# schematic.net
KiCad netlist of a schematic drawn in EasyEDA
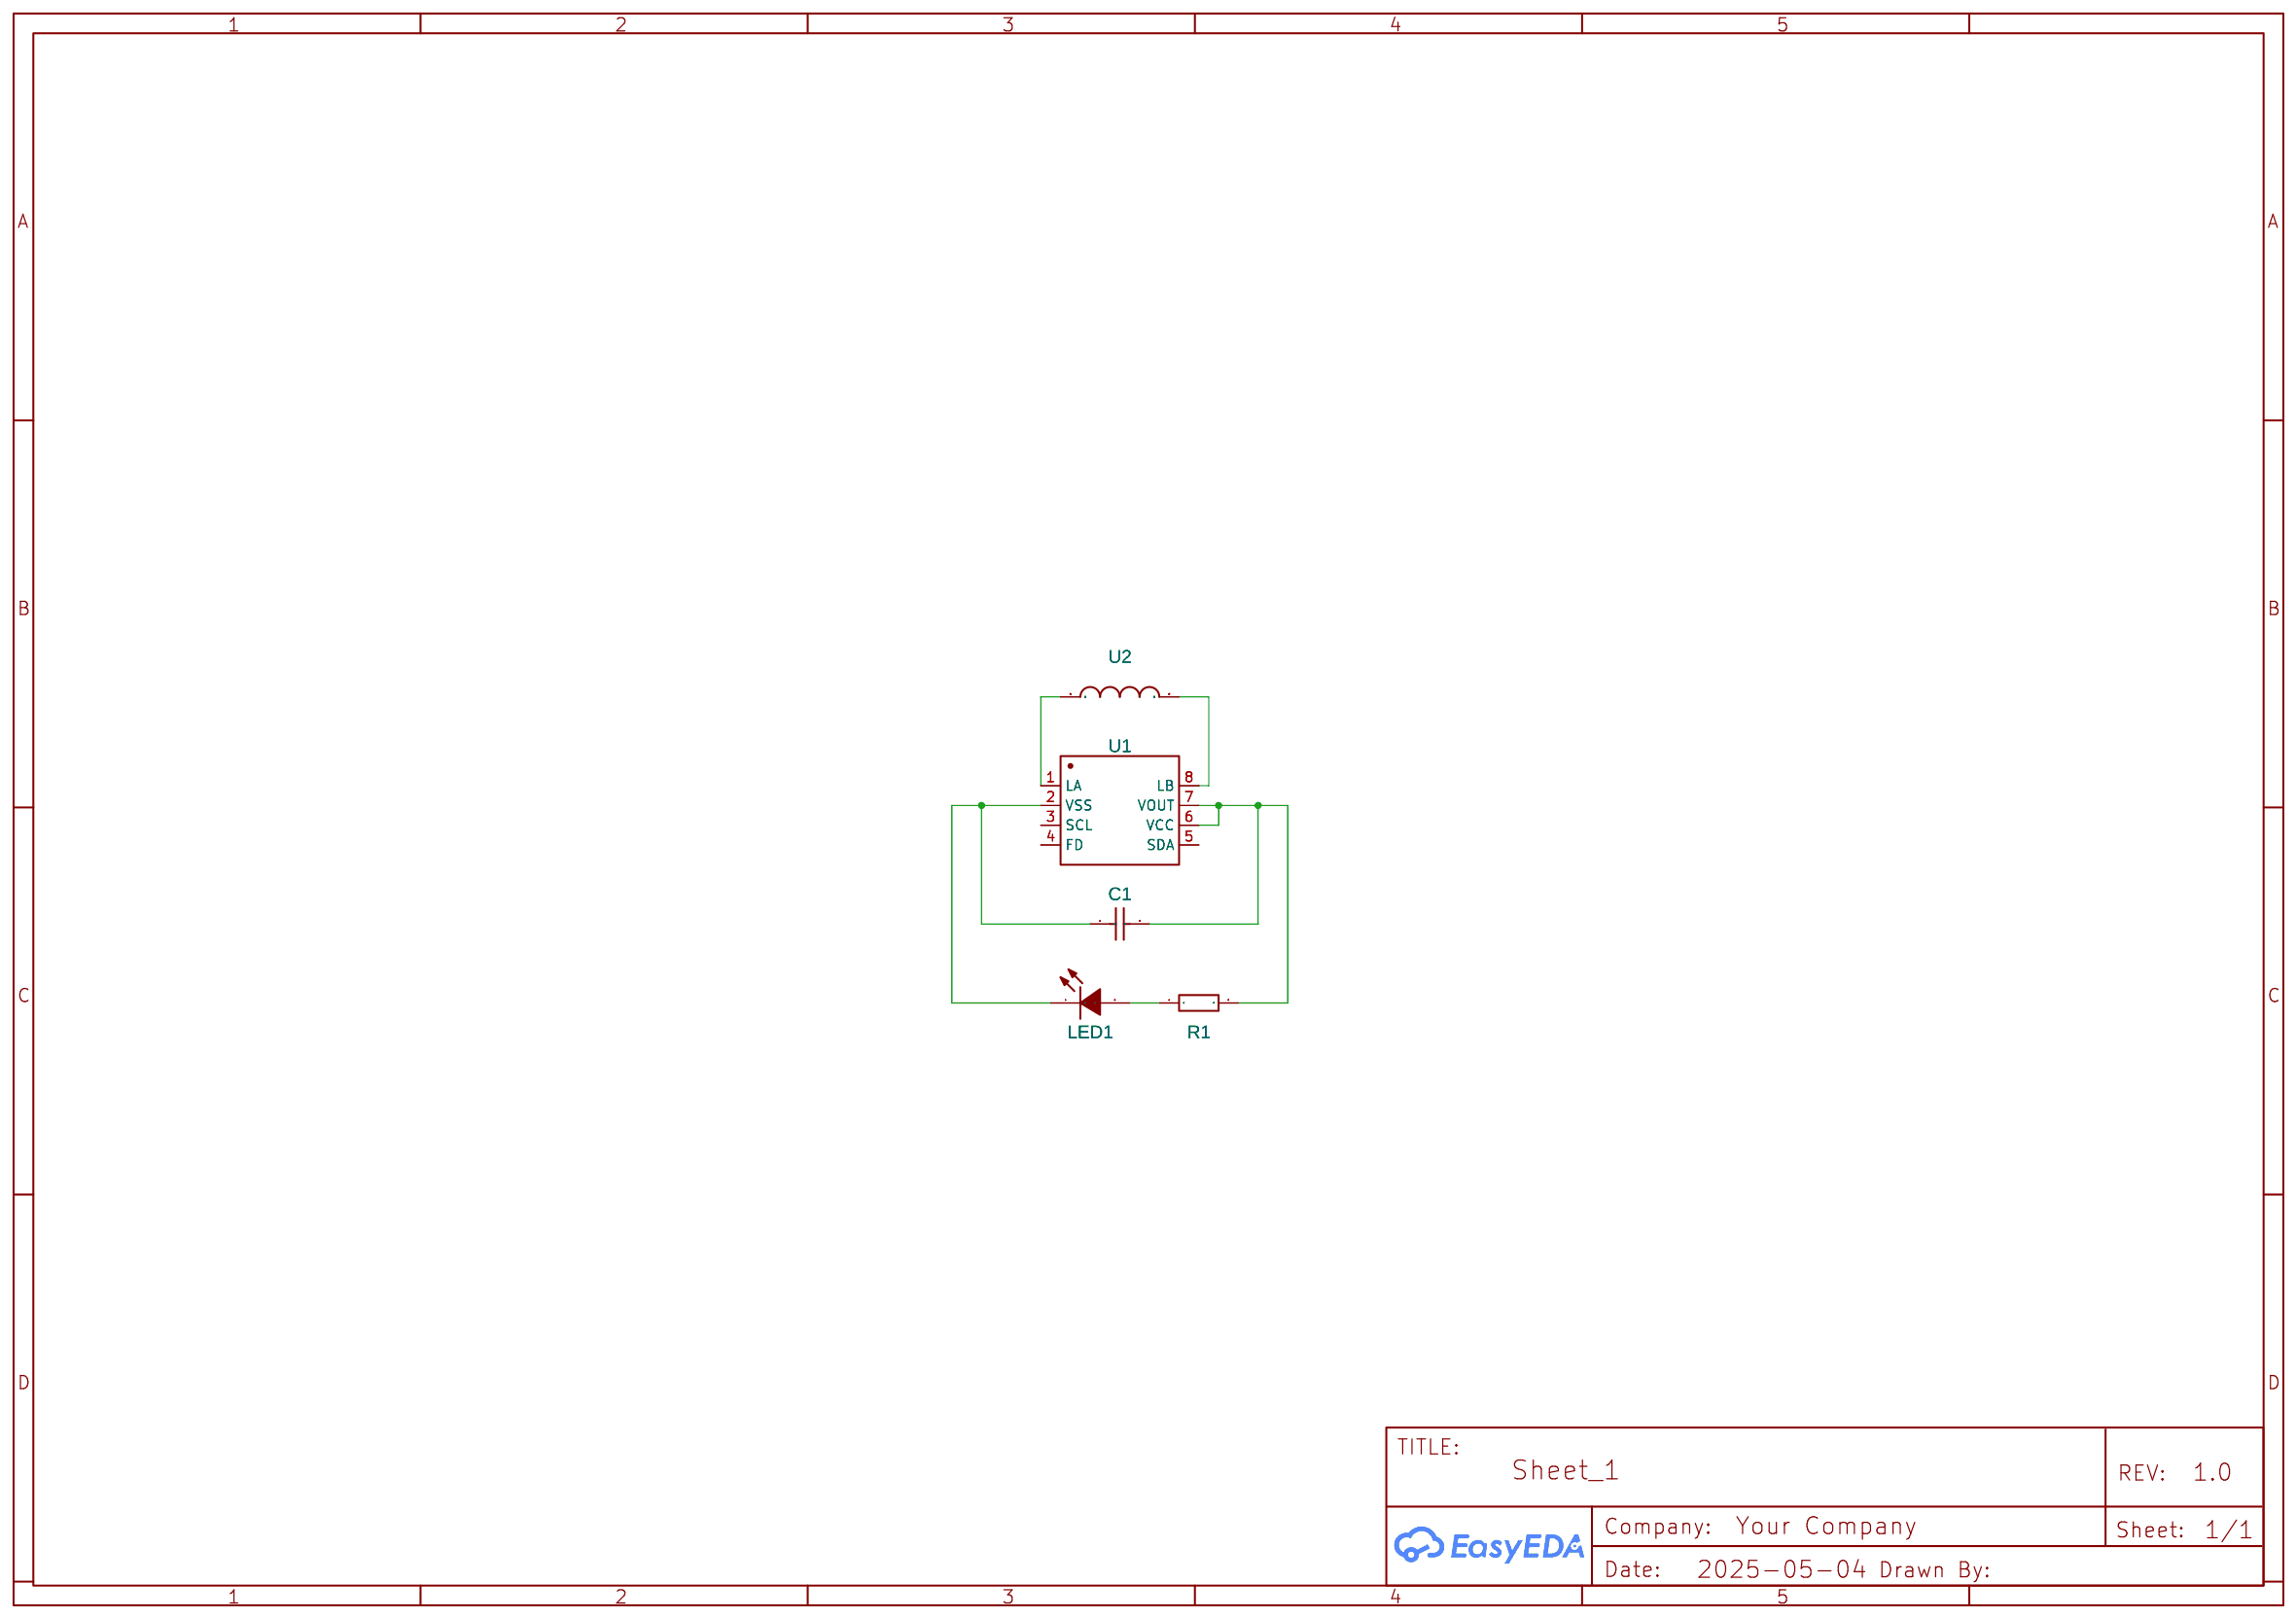
[diagram p0: schematic sheet]

(export (version "E")
  (design (tool "Eeschema 10.0.6"))
  (components
    (comp (ref "C1")
      (value "220nF")
      (fields
        (field (name "Manufacturer Part") "CL10B224KA8NNNC")
        (field (name "Manufacturer") "SAMSUNG(三星)")
      )
      (libsource (lib "") (part "CL10B224KA8NNNC"))
    )
    (comp (ref "LED1")
      (value "LTST-C191KSKT")
      (fields (field (name "Manufacturer") "LITEON(光宝)"))
      (libsource (lib "") (part "LTST-C191KSKT"))
    )
    (comp (ref "R1")
      (value "47Ω")
      (fields
        (field (name "Manufacturer Part") "0603WAF470JT5E")
        (field (name "Manufacturer") "UNI-ROYAL(厚声)")
      )
      (libsource (lib "") (part "0603WAF470JT5E"))
    )
    (comp (ref "U1")
      (value "NT3H2111W0FHKH")
      (fields (field (name "Manufacturer") "NXP(恩智浦)"))
      (libsource (lib "") (part "NT3H2111W0FHKH"))
    )
    (comp (ref "U2") (value "Antenna") (libsource (lib "") (part "Antenna")))
  )
  (nets
    (net (code "1") (name "Net-(LED1-+)") (class "Default")
      (node (ref "LED1") (pin "2") (pinfunction "+_2") (pintype "unspecified"))
      (node (ref "R1") (pin "1") (pinfunction "1_1") (pintype "input"))
    )
    (net (code "2") (name "Net-(LED1--)") (class "Default")
      (node (ref "C1") (pin "1") (pinfunction "1_1") (pintype "input"))
      (node (ref "LED1") (pin "1") (pinfunction "-_1") (pintype "unspecified"))
      (node (ref "U1") (pin "2") (pinfunction "VSS_2") (pintype "unspecified"))
    )
    (net (code "3") (name "Net-(U1-LA)") (class "Default")
      (node (ref "U1") (pin "1") (pinfunction "LA_1") (pintype "unspecified"))
      (node (ref "U2") (pin "P$2") (pinfunction "P$2_P$2") (pintype "unspecified"))
    )
    (net (code "4") (name "Net-(U1-LB)") (class "Default")
      (node (ref "U1") (pin "8") (pinfunction "LB_8") (pintype "unspecified"))
      (node (ref "U2") (pin "P$1") (pinfunction "P$1_P$1") (pintype "unspecified"))
    )
    (net (code "5") (name "Net-(U1-VCC)") (class "Default")
      (node (ref "C1") (pin "2") (pinfunction "2_2") (pintype "input"))
      (node (ref "R1") (pin "2") (pinfunction "2_2") (pintype "input"))
      (node (ref "U1") (pin "6") (pinfunction "VCC_6") (pintype "unspecified"))
      (node (ref "U1") (pin "7") (pinfunction "VOUT_7") (pintype "unspecified"))
    )
    (net (code "6") (name "unconnected-(U1-FD-Pad4)") (class "Default")
      (node (ref "U1") (pin "4") (pinfunction "FD_4") (pintype "unspecified"))
    )
    (net (code "7") (name "unconnected-(U1-SCL-Pad3)") (class "Default")
      (node (ref "U1") (pin "3") (pinfunction "SCL_3") (pintype "unspecified"))
    )
    (net (code "8") (name "unconnected-(U1-SDA-Pad5)") (class "Default")
      (node (ref "U1") (pin "5") (pinfunction "SDA_5") (pintype "unspecified"))
    )
  )
)
